# Schematic.net
KiCad netlist of a schematic drawn in Altium Designer
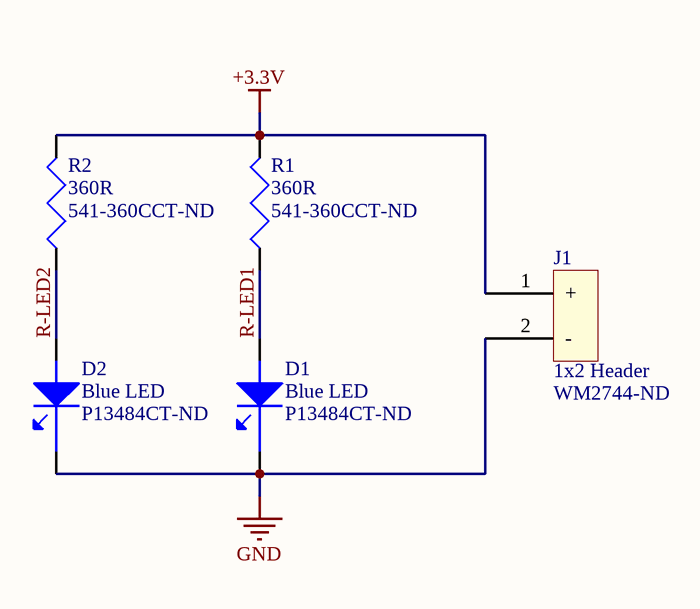
[diagram p0: Schematic.SchDoc]

(export (version "E")
  (design (tool "Eeschema 10.0.6"))
  (components
    (comp (ref "D1")
      (value "Blue LED")
      (footprint "LED0603B")
      (description "LED BLUE UTSS TYPE SMD")
      (fields
        (field (name "MANUFACTURER") "Panasonic SSG")
        (field (name "MANUFACTURER PART NUMBER") "LNJ926W8CRA")
        (field (name "SUPPLIER PART NUMBER 1") "P13484CT-ND")
      )
      (libsource (lib "Schematic_Library") (part "LNJ926W8CRA"))
    )
    (comp (ref "D2")
      (value "Blue LED")
      (footprint "LED0603B")
      (description "LED BLUE UTSS TYPE SMD")
      (fields
        (field (name "MANUFACTURER") "Panasonic SSG")
        (field (name "MANUFACTURER PART NUMBER") "LNJ926W8CRA")
        (field (name "SUPPLIER PART NUMBER 1") "P13484CT-ND")
      )
      (libsource (lib "Schematic_Library") (part "LNJ926W8CRA"))
    )
    (comp (ref "J1")
      (value "1x2 Header")
      (footprint "HDR1X2")
      (description "Conn Wire to Board HDR 2 POS 2.54mm Solder ST Thru-Hole Bag")
      (fields
        (field (name "MANUFACTURER") "Molex")
        (field (name "MANUFACTURER PART NUMBER") "22-29-2021")
        (field (name "SUPPLIER PART NUMBER 1") "WM2744-ND")
      )
      (libsource (lib "Schematic_Library") (part "22-29-2021"))
    )
    (comp (ref "R1")
      (value "360R")
      (footprint "R0805")
      (description "RES SMD 360 OHM 1% 1/8W 0805")
      (fields
        (field (name "MANUFACTURER") "Vishay")
        (field (name "MANUFACTURER PART NUMBER") "CRCW0805360RFKEA")
        (field (name "SUPPLIER PART NUMBER 1") "541-360CCT-ND")
      )
      (libsource (lib "Schematic_Library") (part "CRCW0805360RFKEA"))
    )
    (comp (ref "R2")
      (value "360R")
      (footprint "R0805")
      (description "RES SMD 360 OHM 1% 1/8W 0805")
      (fields
        (field (name "MANUFACTURER") "Vishay")
        (field (name "MANUFACTURER PART NUMBER") "CRCW0805360RFKEA")
        (field (name "SUPPLIER PART NUMBER 1") "541-360CCT-ND")
      )
      (libsource (lib "Schematic_Library") (part "CRCW0805360RFKEA"))
    )
  )
  (nets
    (net (code "1") (name "+3.3V") (class "Default")
      (node (ref "J1") (pin "1") (pinfunction "+_1") (pintype "passive"))
      (node (ref "R1") (pin "2") (pinfunction "2_2") (pintype "passive"))
      (node (ref "R2") (pin "2") (pinfunction "2_2") (pintype "passive"))
    )
    (net (code "2") (name "/R-LED1") (class "Default")
      (node (ref "D1") (pin "2") (pinfunction "2_2") (pintype "passive"))
      (node (ref "R1") (pin "1") (pinfunction "1_1") (pintype "passive"))
    )
    (net (code "3") (name "/R-LED2") (class "Default")
      (node (ref "D2") (pin "2") (pinfunction "2_2") (pintype "passive"))
      (node (ref "R2") (pin "1") (pinfunction "1_1") (pintype "passive"))
    )
    (net (code "4") (name "GND") (class "Default")
      (node (ref "D1") (pin "1") (pinfunction "1_1") (pintype "passive"))
      (node (ref "D2") (pin "1") (pinfunction "1_1") (pintype "passive"))
      (node (ref "J1") (pin "2") (pinfunction "-_2") (pintype "passive"))
    )
  )
)
